# hdmi.net
KiCad netlist of a schematic drawn in Altium Designer
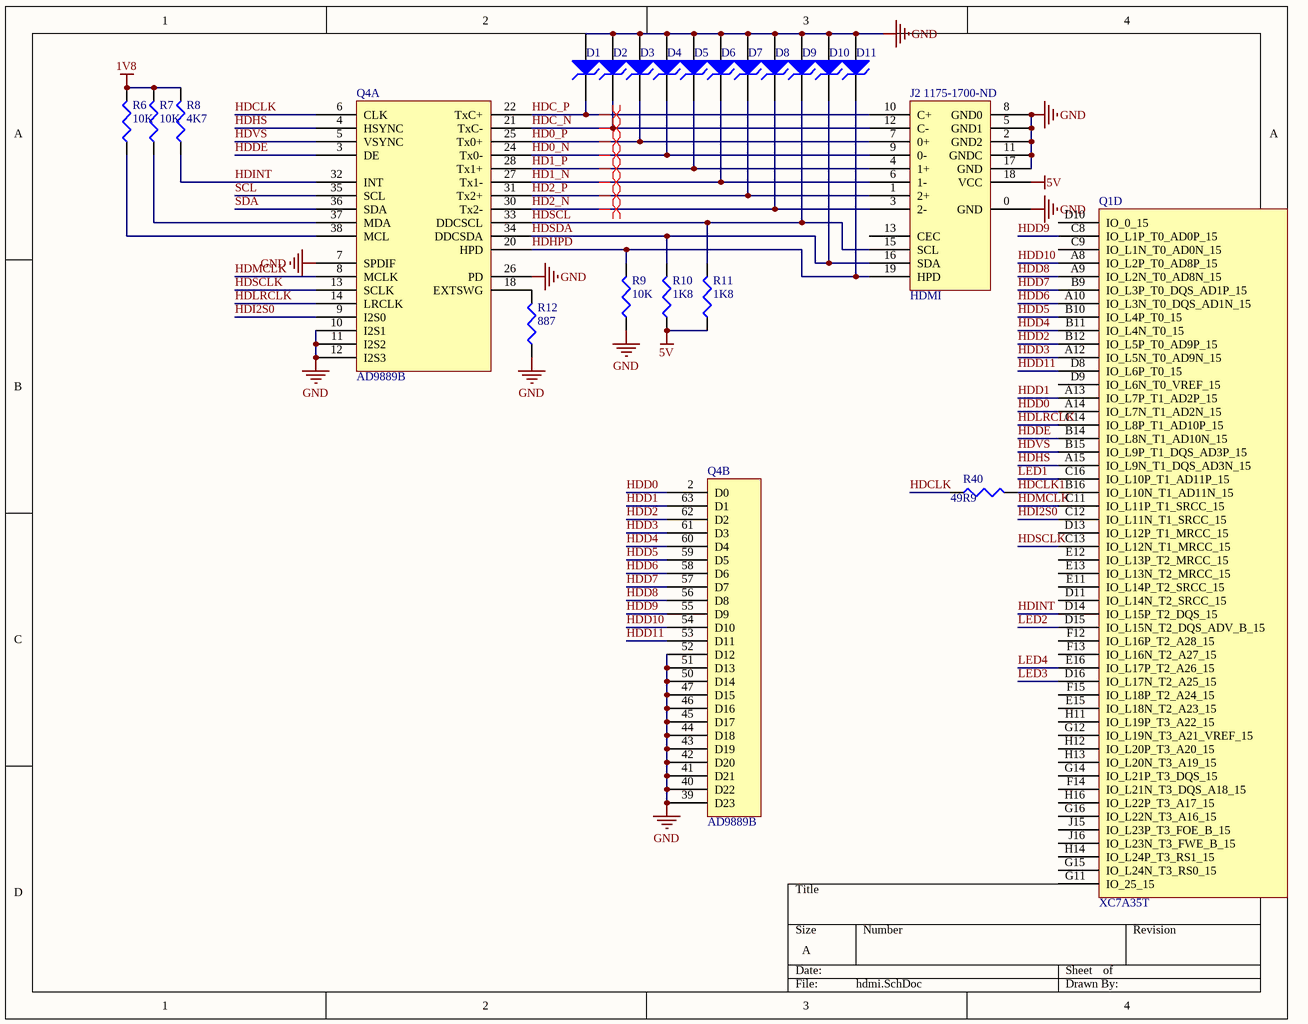
[diagram p0: hdmi.SchDoc]

(export (version "E")
  (design (tool "Eeschema 10.0.6"))
  (components
    (comp (ref "D1")
      (value "EZAEG2A")
      (footprint "CAPC1005X55N")
      (description "Zener Diode")
      (fields (field (name "PUBLISHER") "Altium Limited"))
      (libsource (lib "Miscellaneous Devices") (part "D Zener"))
    )
    (comp (ref "D2")
      (value "EZAEG2A")
      (footprint "CAPC1005X55N")
      (description "Zener Diode")
      (fields (field (name "PUBLISHER") "Altium Limited"))
      (libsource (lib "Miscellaneous Devices") (part "D Zener"))
    )
    (comp (ref "D3")
      (value "EZAEG2A")
      (footprint "CAPC1005X55N")
      (description "Zener Diode")
      (fields (field (name "PUBLISHER") "Altium Limited"))
      (libsource (lib "Miscellaneous Devices") (part "D Zener"))
    )
    (comp (ref "D4")
      (value "EZAEG2A")
      (footprint "CAPC1005X55N")
      (description "Zener Diode")
      (fields (field (name "PUBLISHER") "Altium Limited"))
      (libsource (lib "Miscellaneous Devices") (part "D Zener"))
    )
    (comp (ref "D5")
      (value "EZAEG2A")
      (footprint "CAPC1005X55N")
      (description "Zener Diode")
      (fields (field (name "PUBLISHER") "Altium Limited"))
      (libsource (lib "Miscellaneous Devices") (part "D Zener"))
    )
    (comp (ref "D6")
      (value "EZAEG2A")
      (footprint "CAPC1005X55N")
      (description "Zener Diode")
      (fields (field (name "PUBLISHER") "Altium Limited"))
      (libsource (lib "Miscellaneous Devices") (part "D Zener"))
    )
    (comp (ref "D7")
      (value "EZAEG2A")
      (footprint "CAPC1005X55N")
      (description "Zener Diode")
      (fields (field (name "PUBLISHER") "Altium Limited"))
      (libsource (lib "Miscellaneous Devices") (part "D Zener"))
    )
    (comp (ref "D8")
      (value "EZAEG2A")
      (footprint "CAPC1005X55N")
      (description "Zener Diode")
      (fields (field (name "PUBLISHER") "Altium Limited"))
      (libsource (lib "Miscellaneous Devices") (part "D Zener"))
    )
    (comp (ref "D9")
      (value "EZAEG2A")
      (footprint "CAPC1005X55N")
      (description "Zener Diode")
      (fields (field (name "PUBLISHER") "Altium Limited"))
      (libsource (lib "Miscellaneous Devices") (part "D Zener"))
    )
    (comp (ref "D10")
      (value "EZAEG2A")
      (footprint "CAPC1005X55N")
      (description "Zener Diode")
      (fields (field (name "PUBLISHER") "Altium Limited"))
      (libsource (lib "Miscellaneous Devices") (part "D Zener"))
    )
    (comp (ref "D11")
      (value "EZAEG2A")
      (footprint "CAPC1005X55N")
      (description "Zener Diode")
      (fields (field (name "PUBLISHER") "Altium Limited"))
      (libsource (lib "Miscellaneous Devices") (part "D Zener"))
    )
    (comp (ref "J2")
      (value "HDMI")
      (footprint "2000-1-1-20-00-BK")
      (fields (field (name "SUPPLIER PART NUMBER 1") "1175-1700-ND"))
      (libsource (lib "schlib") (part "HDMI"))
    )
    (comp (ref "Q1") (value "XC7A35T") (libsource (lib "schlib") (part "XC7A35T")))
    (comp (ref "Q4")
      (value "AD9889B")
      (footprint "QFN50P900X875X100_HS-65N")
      (libsource (lib "schlib") (part "AD9889B"))
    )
    (comp (ref "R6")
      (value "10K")
      (footprint "CAPC1608X90N")
      (description "Resistor")
      (fields (field (name "Comment") "Res3") (field (name "PUBLISHER") "Altium Limited"))
      (libsource (lib "Miscellaneous Devices") (part "Res3"))
    )
    (comp (ref "R7")
      (value "10K")
      (footprint "CAPC1608X90N")
      (description "Resistor")
      (fields (field (name "Comment") "Res3") (field (name "PUBLISHER") "Altium Limited"))
      (libsource (lib "Miscellaneous Devices") (part "Res3"))
    )
    (comp (ref "R8")
      (value "4K7")
      (footprint "CAPC1608X90N")
      (description "Resistor")
      (fields (field (name "Comment") "Res3") (field (name "PUBLISHER") "Altium Limited"))
      (libsource (lib "Miscellaneous Devices") (part "Res3"))
    )
    (comp (ref "R9")
      (value "10K")
      (footprint "CAPC1608X90N")
      (description "Resistor")
      (fields (field (name "Comment") "Res3") (field (name "PUBLISHER") "Altium Limited"))
      (libsource (lib "Miscellaneous Devices") (part "Res3"))
    )
    (comp (ref "R10")
      (value "1K8")
      (footprint "CAPC1608X90N")
      (description "Resistor")
      (fields (field (name "Comment") "Res3") (field (name "PUBLISHER") "Altium Limited"))
      (libsource (lib "Miscellaneous Devices") (part "Res3"))
    )
    (comp (ref "R11")
      (value "1K8")
      (footprint "CAPC1608X90N")
      (description "Resistor")
      (fields (field (name "Comment") "Res3") (field (name "PUBLISHER") "Altium Limited"))
      (libsource (lib "Miscellaneous Devices") (part "Res3"))
    )
    (comp (ref "R12")
      (value "887")
      (footprint "CAPC1608X90N")
      (description "Resistor")
      (fields (field (name "Comment") "Res3") (field (name "PUBLISHER") "Altium Limited"))
      (libsource (lib "Miscellaneous Devices") (part "Res3"))
    )
    (comp (ref "R40")
      (value "49R9")
      (footprint "CAPC1005X06L")
      (description "Resistor")
      (fields (field (name "Comment") "Res3") (field (name "PUBLISHER") "Altium Limited"))
      (libsource (lib "Miscellaneous Devices") (part "Res3"))
    )
  )
  (nets
    (net (code "1") (name "/HD0_N") (class "Default")
      (node (ref "D4") (pin "2") (pinfunction "K_2") (pintype "passive"))
      (node (ref "J2") (pin "9") (pinfunction "0-_9") (pintype "passive"))
      (node (ref "Q4") (pin "24") (pinfunction "Tx0-_24") (pintype "passive"))
    )
    (net (code "2") (name "/HD0_P") (class "Default")
      (node (ref "D3") (pin "2") (pinfunction "K_2") (pintype "passive"))
      (node (ref "J2") (pin "7") (pinfunction "0+_7") (pintype "passive"))
      (node (ref "Q4") (pin "25") (pinfunction "Tx0+_25") (pintype "passive"))
    )
    (net (code "3") (name "/HD1_N") (class "Default")
      (node (ref "D6") (pin "2") (pinfunction "K_2") (pintype "passive"))
      (node (ref "J2") (pin "6") (pinfunction "1-_6") (pintype "passive"))
      (node (ref "Q4") (pin "27") (pinfunction "Tx1-_27") (pintype "passive"))
    )
    (net (code "4") (name "/HD1_P") (class "Default")
      (node (ref "D5") (pin "2") (pinfunction "K_2") (pintype "passive"))
      (node (ref "J2") (pin "4") (pinfunction "1+_4") (pintype "passive"))
      (node (ref "Q4") (pin "28") (pinfunction "Tx1+_28") (pintype "passive"))
    )
    (net (code "5") (name "/HD2_N") (class "Default")
      (node (ref "D8") (pin "2") (pinfunction "K_2") (pintype "passive"))
      (node (ref "J2") (pin "3") (pinfunction "2-_3") (pintype "passive"))
      (node (ref "Q4") (pin "30") (pinfunction "Tx2-_30") (pintype "passive"))
    )
    (net (code "6") (name "/HD2_P") (class "Default")
      (node (ref "D7") (pin "2") (pinfunction "K_2") (pintype "passive"))
      (node (ref "J2") (pin "1") (pinfunction "2+_1") (pintype "passive"))
      (node (ref "Q4") (pin "31") (pinfunction "Tx2+_31") (pintype "passive"))
    )
    (net (code "7") (name "/HDCLK") (class "Default")
      (node (ref "Q4") (pin "6") (pinfunction "CLK_6") (pintype "passive"))
      (node (ref "R40") (pin "1") (pinfunction "1_1") (pintype "passive"))
    )
    (net (code "8") (name "/HDCLK1") (class "Default")
      (node (ref "Q1") (pin "B16") (pinfunction "IO_L10N_T1_AD11N_15_B16") (pintype "passive"))
      (node (ref "R40") (pin "2") (pinfunction "2_2") (pintype "passive"))
    )
    (net (code "9") (name "/HDC_N") (class "Default")
      (node (ref "D2") (pin "2") (pinfunction "K_2") (pintype "passive"))
      (node (ref "J2") (pin "12") (pinfunction "C-_12") (pintype "passive"))
      (node (ref "Q4") (pin "21") (pinfunction "TxC-_21") (pintype "passive"))
    )
    (net (code "10") (name "/HDC_P") (class "Default")
      (node (ref "D1") (pin "2") (pinfunction "K_2") (pintype "passive"))
      (node (ref "J2") (pin "10") (pinfunction "C+_10") (pintype "passive"))
      (node (ref "Q4") (pin "22") (pinfunction "TxC+_22") (pintype "passive"))
    )
    (net (code "11") (name "/HDD0") (class "Default")
      (node (ref "Q1") (pin "A14") (pinfunction "IO_L7N_T1_AD2N_15_A14") (pintype "passive"))
      (node (ref "Q4") (pin "2") (pinfunction "D0_2") (pintype "passive"))
    )
    (net (code "12") (name "/HDD1") (class "Default")
      (node (ref "Q1") (pin "A13") (pinfunction "IO_L7P_T1_AD2P_15_A13") (pintype "passive"))
      (node (ref "Q4") (pin "63") (pinfunction "D1_63") (pintype "passive"))
    )
    (net (code "13") (name "/HDD2") (class "Default")
      (node (ref "Q1") (pin "B12") (pinfunction "IO_L5P_T0_AD9P_15_B12") (pintype "passive"))
      (node (ref "Q4") (pin "62") (pinfunction "D2_62") (pintype "passive"))
    )
    (net (code "14") (name "/HDD3") (class "Default")
      (node (ref "Q1") (pin "A12") (pinfunction "IO_L5N_T0_AD9N_15_A12") (pintype "passive"))
      (node (ref "Q4") (pin "61") (pinfunction "D3_61") (pintype "passive"))
    )
    (net (code "15") (name "/HDD4") (class "Default")
      (node (ref "Q1") (pin "B11") (pinfunction "IO_L4N_T0_15_B11") (pintype "passive"))
      (node (ref "Q4") (pin "60") (pinfunction "D4_60") (pintype "passive"))
    )
    (net (code "16") (name "/HDD5") (class "Default")
      (node (ref "Q1") (pin "B10") (pinfunction "IO_L4P_T0_15_B10") (pintype "passive"))
      (node (ref "Q4") (pin "59") (pinfunction "D5_59") (pintype "passive"))
    )
    (net (code "17") (name "/HDD6") (class "Default")
      (node (ref "Q1") (pin "A10") (pinfunction "IO_L3N_T0_DQS_AD1N_15_A10") (pintype "passive"))
      (node (ref "Q4") (pin "58") (pinfunction "D6_58") (pintype "passive"))
    )
    (net (code "18") (name "/HDD7") (class "Default")
      (node (ref "Q1") (pin "B9") (pinfunction "IO_L3P_T0_DQS_AD1P_15_B9") (pintype "passive"))
      (node (ref "Q4") (pin "57") (pinfunction "D7_57") (pintype "passive"))
    )
    (net (code "19") (name "/HDD8") (class "Default")
      (node (ref "Q1") (pin "A9") (pinfunction "IO_L2N_T0_AD8N_15_A9") (pintype "passive"))
      (node (ref "Q4") (pin "56") (pinfunction "D8_56") (pintype "passive"))
    )
    (net (code "20") (name "/HDD9") (class "Default")
      (node (ref "Q1") (pin "C8") (pinfunction "IO_L1P_T0_AD0P_15_C8") (pintype "passive"))
      (node (ref "Q4") (pin "55") (pinfunction "D9_55") (pintype "passive"))
    )
    (net (code "21") (name "/HDD10") (class "Default")
      (node (ref "Q1") (pin "A8") (pinfunction "IO_L2P_T0_AD8P_15_A8") (pintype "passive"))
      (node (ref "Q4") (pin "54") (pinfunction "D10_54") (pintype "passive"))
    )
    (net (code "22") (name "/HDD11") (class "Default")
      (node (ref "Q1") (pin "D8") (pinfunction "IO_L6P_T0_15_D8") (pintype "passive"))
      (node (ref "Q4") (pin "53") (pinfunction "D11_53") (pintype "passive"))
    )
    (net (code "23") (name "/HDDE") (class "Default")
      (node (ref "Q1") (pin "B14") (pinfunction "IO_L8N_T1_AD10N_15_B14") (pintype "passive"))
      (node (ref "Q4") (pin "3") (pinfunction "DE_3") (pintype "passive"))
    )
    (net (code "24") (name "/HDHPD") (class "Default")
      (node (ref "D11") (pin "2") (pinfunction "K_2") (pintype "passive"))
      (node (ref "J2") (pin "19") (pinfunction "HPD_19") (pintype "passive"))
      (node (ref "Q4") (pin "20") (pinfunction "HPD_20") (pintype "passive"))
      (node (ref "R9") (pin "2") (pinfunction "2_2") (pintype "passive"))
    )
    (net (code "25") (name "/HDHS") (class "Default")
      (node (ref "Q1") (pin "A15") (pinfunction "IO_L9N_T1_DQS_AD3N_15_A15") (pintype "passive"))
      (node (ref "Q4") (pin "4") (pinfunction "HSYNC_4") (pintype "passive"))
    )
    (net (code "26") (name "/HDI2S0") (class "Default")
      (node (ref "Q1") (pin "C12") (pinfunction "IO_L11N_T1_SRCC_15_C12") (pintype "passive"))
      (node (ref "Q4") (pin "9") (pinfunction "I2S0_9") (pintype "passive"))
    )
    (net (code "27") (name "/HDINT") (class "Default")
      (node (ref "Q1") (pin "D14") (pinfunction "IO_L15P_T2_DQS_15_D14") (pintype "passive"))
      (node (ref "Q4") (pin "32") (pinfunction "INT_32") (pintype "passive"))
      (node (ref "R8") (pin "1") (pinfunction "1_1") (pintype "passive"))
    )
    (net (code "28") (name "/HDLRCLK") (class "Default")
      (node (ref "Q1") (pin "C14") (pinfunction "IO_L8P_T1_AD10P_15_C14") (pintype "passive"))
      (node (ref "Q4") (pin "14") (pinfunction "LRCLK_14") (pintype "passive"))
    )
    (net (code "29") (name "/HDMCLK") (class "Default")
      (node (ref "Q1") (pin "C11") (pinfunction "IO_L11P_T1_SRCC_15_C11") (pintype "passive"))
      (node (ref "Q4") (pin "8") (pinfunction "MCLK_8") (pintype "passive"))
    )
    (net (code "30") (name "/HDSCL") (class "Default")
      (node (ref "D9") (pin "2") (pinfunction "K_2") (pintype "passive"))
      (node (ref "J2") (pin "15") (pinfunction "SCL_15") (pintype "passive"))
      (node (ref "Q4") (pin "33") (pinfunction "DDCSCL_33") (pintype "passive"))
      (node (ref "R11") (pin "2") (pinfunction "2_2") (pintype "passive"))
    )
    (net (code "31") (name "/HDSCLK") (class "Default")
      (node (ref "Q1") (pin "C13") (pinfunction "IO_L12N_T1_MRCC_15_C13") (pintype "passive"))
      (node (ref "Q4") (pin "13") (pinfunction "SCLK_13") (pintype "passive"))
    )
    (net (code "32") (name "/HDSDA") (class "Default")
      (node (ref "D10") (pin "2") (pinfunction "K_2") (pintype "passive"))
      (node (ref "J2") (pin "16") (pinfunction "SDA_16") (pintype "passive"))
      (node (ref "Q4") (pin "34") (pinfunction "DDCSDA_34") (pintype "passive"))
      (node (ref "R10") (pin "2") (pinfunction "2_2") (pintype "passive"))
    )
    (net (code "33") (name "/HDVS") (class "Default")
      (node (ref "Q1") (pin "B15") (pinfunction "IO_L9P_T1_DQS_AD3P_15_B15") (pintype "passive"))
      (node (ref "Q4") (pin "5") (pinfunction "VSYNC_5") (pintype "passive"))
    )
    (net (code "34") (name "/LED1") (class "Default")
      (node (ref "Q1") (pin "C16") (pinfunction "IO_L10P_T1_AD11P_15_C16") (pintype "passive"))
    )
    (net (code "35") (name "/LED2") (class "Default")
      (node (ref "Q1") (pin "D15") (pinfunction "IO_L15N_T2_DQS_ADV_B_15_D15") (pintype "passive"))
    )
    (net (code "36") (name "/LED3") (class "Default")
      (node (ref "Q1") (pin "D16") (pinfunction "IO_L17N_T2_A25_15_D16") (pintype "passive"))
    )
    (net (code "37") (name "/LED4") (class "Default")
      (node (ref "Q1") (pin "E16") (pinfunction "IO_L17P_T2_A26_15_E16") (pintype "passive"))
    )
    (net (code "38") (name "/SCL") (class "Default")
      (node (ref "Q4") (pin "35") (pinfunction "SCL_35") (pintype "passive"))
    )
    (net (code "39") (name "/SDA") (class "Default")
      (node (ref "Q4") (pin "36") (pinfunction "SDA_36") (pintype "passive"))
    )
    (net (code "40") (name "1V8") (class "Default")
      (node (ref "R6") (pin "2") (pinfunction "2_2") (pintype "passive"))
      (node (ref "R7") (pin "2") (pinfunction "2_2") (pintype "passive"))
      (node (ref "R8") (pin "2") (pinfunction "2_2") (pintype "passive"))
    )
    (net (code "41") (name "5V") (class "Default")
      (node (ref "J2") (pin "18") (pinfunction "VCC_18") (pintype "passive"))
      (node (ref "R10") (pin "1") (pinfunction "1_1") (pintype "passive"))
      (node (ref "R11") (pin "1") (pinfunction "1_1") (pintype "passive"))
    )
    (net (code "42") (name "GND") (class "Default")
      (node (ref "D1") (pin "1") (pinfunction "A_1") (pintype "passive"))
      (node (ref "D10") (pin "1") (pinfunction "A_1") (pintype "passive"))
      (node (ref "D11") (pin "1") (pinfunction "A_1") (pintype "passive"))
      (node (ref "D2") (pin "1") (pinfunction "A_1") (pintype "passive"))
      (node (ref "D3") (pin "1") (pinfunction "A_1") (pintype "passive"))
      (node (ref "D4") (pin "1") (pinfunction "A_1") (pintype "passive"))
      (node (ref "D5") (pin "1") (pinfunction "A_1") (pintype "passive"))
      (node (ref "D6") (pin "1") (pinfunction "A_1") (pintype "passive"))
      (node (ref "D7") (pin "1") (pinfunction "A_1") (pintype "passive"))
      (node (ref "D8") (pin "1") (pinfunction "A_1") (pintype "passive"))
      (node (ref "D9") (pin "1") (pinfunction "A_1") (pintype "passive"))
      (node (ref "J2") (pin "0") (pinfunction "GND_0") (pintype "passive"))
      (node (ref "J2") (pin "11") (pinfunction "GNDC_11") (pintype "passive"))
      (node (ref "J2") (pin "17") (pinfunction "GND_17") (pintype "passive"))
      (node (ref "J2") (pin "2") (pinfunction "GND2_2") (pintype "passive"))
      (node (ref "J2") (pin "5") (pinfunction "GND1_5") (pintype "passive"))
      (node (ref "J2") (pin "8") (pinfunction "GND0_8") (pintype "passive"))
      (node (ref "Q4") (pin "10") (pinfunction "I2S1_10") (pintype "passive"))
      (node (ref "Q4") (pin "11") (pinfunction "I2S2_11") (pintype "passive"))
      (node (ref "Q4") (pin "12") (pinfunction "I2S3_12") (pintype "passive"))
      (node (ref "Q4") (pin "26") (pinfunction "PD_26") (pintype "passive"))
      (node (ref "Q4") (pin "39") (pinfunction "D23_39") (pintype "passive"))
      (node (ref "Q4") (pin "40") (pinfunction "D22_40") (pintype "passive"))
      (node (ref "Q4") (pin "41") (pinfunction "D21_41") (pintype "passive"))
      (node (ref "Q4") (pin "42") (pinfunction "D20_42") (pintype "passive"))
      (node (ref "Q4") (pin "43") (pinfunction "D19_43") (pintype "passive"))
      (node (ref "Q4") (pin "44") (pinfunction "D18_44") (pintype "passive"))
      (node (ref "Q4") (pin "45") (pinfunction "D17_45") (pintype "passive"))
      (node (ref "Q4") (pin "46") (pinfunction "D16_46") (pintype "passive"))
      (node (ref "Q4") (pin "47") (pinfunction "D15_47") (pintype "passive"))
      (node (ref "Q4") (pin "50") (pinfunction "D14_50") (pintype "passive"))
      (node (ref "Q4") (pin "51") (pinfunction "D13_51") (pintype "passive"))
      (node (ref "Q4") (pin "52") (pinfunction "D12_52") (pintype "passive"))
      (node (ref "Q4") (pin "7") (pinfunction "SPDIF_7") (pintype "passive"))
      (node (ref "R12") (pin "1") (pinfunction "1_1") (pintype "passive"))
      (node (ref "R9") (pin "1") (pinfunction "1_1") (pintype "passive"))
    )
    (net (code "43") (name "Net-(Q4A-EXTSWG)") (class "Default")
      (node (ref "Q4") (pin "18") (pinfunction "EXTSWG_18") (pintype "passive"))
      (node (ref "R12") (pin "2") (pinfunction "2_2") (pintype "passive"))
    )
    (net (code "44") (name "Net-(Q4A-MCL)") (class "Default")
      (node (ref "Q4") (pin "38") (pinfunction "MCL_38") (pintype "passive"))
      (node (ref "R6") (pin "1") (pinfunction "1_1") (pintype "passive"))
    )
    (net (code "45") (name "Net-(Q4A-MDA)") (class "Default")
      (node (ref "Q4") (pin "37") (pinfunction "MDA_37") (pintype "passive"))
      (node (ref "R7") (pin "1") (pinfunction "1_1") (pintype "passive"))
    )
    (net (code "46") (name "unconnected-(J2-CEC-Pad13)") (class "Default")
      (node (ref "J2") (pin "13") (pinfunction "CEC_13") (pintype "passive"))
    )
    (net (code "47") (name "unconnected-(Q1D-IO_0_15-PadD10)") (class "Default")
      (node (ref "Q1") (pin "D10") (pinfunction "IO_0_15_D10") (pintype "passive"))
    )
    (net (code "48") (name "unconnected-(Q1D-IO_25_15-PadG11)") (class "Default")
      (node (ref "Q1") (pin "G11") (pinfunction "IO_25_15_G11") (pintype "passive"))
    )
    (net (code "49") (name "unconnected-(Q1D-IO_L1N_T0_AD0N_15-PadC9)") (class "Default")
      (node (ref "Q1") (pin "C9") (pinfunction "IO_L1N_T0_AD0N_15_C9") (pintype "passive"))
    )
    (net (code "50") (name "unconnected-(Q1D-IO_L6N_T0_VREF_15-PadD9)") (class "Default")
      (node (ref "Q1") (pin "D9") (pinfunction "IO_L6N_T0_VREF_15_D9") (pintype "passive"))
    )
    (net (code "51") (name "unconnected-(Q1D-IO_L12P_T1_MRCC_15-PadD13)") (class "Default")
      (node (ref "Q1") (pin "D13") (pinfunction "IO_L12P_T1_MRCC_15_D13") (pintype "passive"))
    )
    (net (code "52") (name "unconnected-(Q1D-IO_L13N_T2_MRCC_15-PadE13)") (class "Default")
      (node (ref "Q1") (pin "E13") (pinfunction "IO_L13N_T2_MRCC_15_E13") (pintype "passive"))
    )
    (net (code "53") (name "unconnected-(Q1D-IO_L13P_T2_MRCC_15-PadE12)") (class "Default")
      (node (ref "Q1") (pin "E12") (pinfunction "IO_L13P_T2_MRCC_15_E12") (pintype "passive"))
    )
    (net (code "54") (name "unconnected-(Q1D-IO_L14N_T2_SRCC_15-PadD11)") (class "Default")
      (node (ref "Q1") (pin "D11") (pinfunction "IO_L14N_T2_SRCC_15_D11") (pintype "passive"))
    )
    (net (code "55") (name "unconnected-(Q1D-IO_L14P_T2_SRCC_15-PadE11)") (class "Default")
      (node (ref "Q1") (pin "E11") (pinfunction "IO_L14P_T2_SRCC_15_E11") (pintype "passive"))
    )
    (net (code "56") (name "unconnected-(Q1D-IO_L16N_T2_A27_15-PadF13)") (class "Default")
      (node (ref "Q1") (pin "F13") (pinfunction "IO_L16N_T2_A27_15_F13") (pintype "passive"))
    )
    (net (code "57") (name "unconnected-(Q1D-IO_L16P_T2_A28_15-PadF12)") (class "Default")
      (node (ref "Q1") (pin "F12") (pinfunction "IO_L16P_T2_A28_15_F12") (pintype "passive"))
    )
    (net (code "58") (name "unconnected-(Q1D-IO_L18N_T2_A23_15-PadE15)") (class "Default")
      (node (ref "Q1") (pin "E15") (pinfunction "IO_L18N_T2_A23_15_E15") (pintype "passive"))
    )
    (net (code "59") (name "unconnected-(Q1D-IO_L18P_T2_A24_15-PadF15)") (class "Default")
      (node (ref "Q1") (pin "F15") (pinfunction "IO_L18P_T2_A24_15_F15") (pintype "passive"))
    )
    (net (code "60") (name "unconnected-(Q1D-IO_L19N_T3_A21_VREF_15-PadG12)") (class "Default")
      (node (ref "Q1") (pin "G12") (pinfunction "IO_L19N_T3_A21_VREF_15_G12") (pintype "passive"))
    )
    (net (code "61") (name "unconnected-(Q1D-IO_L19P_T3_A22_15-PadH11)") (class "Default")
      (node (ref "Q1") (pin "H11") (pinfunction "IO_L19P_T3_A22_15_H11") (pintype "passive"))
    )
    (net (code "62") (name "unconnected-(Q1D-IO_L20N_T3_A19_15-PadH13)") (class "Default")
      (node (ref "Q1") (pin "H13") (pinfunction "IO_L20N_T3_A19_15_H13") (pintype "passive"))
    )
    (net (code "63") (name "unconnected-(Q1D-IO_L20P_T3_A20_15-PadH12)") (class "Default")
      (node (ref "Q1") (pin "H12") (pinfunction "IO_L20P_T3_A20_15_H12") (pintype "passive"))
    )
    (net (code "64") (name "unconnected-(Q1D-IO_L21N_T3_DQS_A18_15-PadF14)") (class "Default")
      (node (ref "Q1") (pin "F14") (pinfunction "IO_L21N_T3_DQS_A18_15_F14") (pintype "passive"))
    )
    (net (code "65") (name "unconnected-(Q1D-IO_L21P_T3_DQS_15-PadG14)") (class "Default")
      (node (ref "Q1") (pin "G14") (pinfunction "IO_L21P_T3_DQS_15_G14") (pintype "passive"))
    )
    (net (code "66") (name "unconnected-(Q1D-IO_L22N_T3_A16_15-PadG16)") (class "Default")
      (node (ref "Q1") (pin "G16") (pinfunction "IO_L22N_T3_A16_15_G16") (pintype "passive"))
    )
    (net (code "67") (name "unconnected-(Q1D-IO_L22P_T3_A17_15-PadH16)") (class "Default")
      (node (ref "Q1") (pin "H16") (pinfunction "IO_L22P_T3_A17_15_H16") (pintype "passive"))
    )
    (net (code "68") (name "unconnected-(Q1D-IO_L23N_T3_FWE_B_15-PadJ16)") (class "Default")
      (node (ref "Q1") (pin "J16") (pinfunction "IO_L23N_T3_FWE_B_15_J16") (pintype "passive"))
    )
    (net (code "69") (name "unconnected-(Q1D-IO_L23P_T3_FOE_B_15-PadJ15)") (class "Default")
      (node (ref "Q1") (pin "J15") (pinfunction "IO_L23P_T3_FOE_B_15_J15") (pintype "passive"))
    )
    (net (code "70") (name "unconnected-(Q1D-IO_L24N_T3_RS0_15-PadG15)") (class "Default")
      (node (ref "Q1") (pin "G15") (pinfunction "IO_L24N_T3_RS0_15_G15") (pintype "passive"))
    )
    (net (code "71") (name "unconnected-(Q1D-IO_L24P_T3_RS1_15-PadH14)") (class "Default")
      (node (ref "Q1") (pin "H14") (pinfunction "IO_L24P_T3_RS1_15_H14") (pintype "passive"))
    )
  )
)
